# Sheet1.net
KiCad netlist of a schematic drawn in Altium Designer
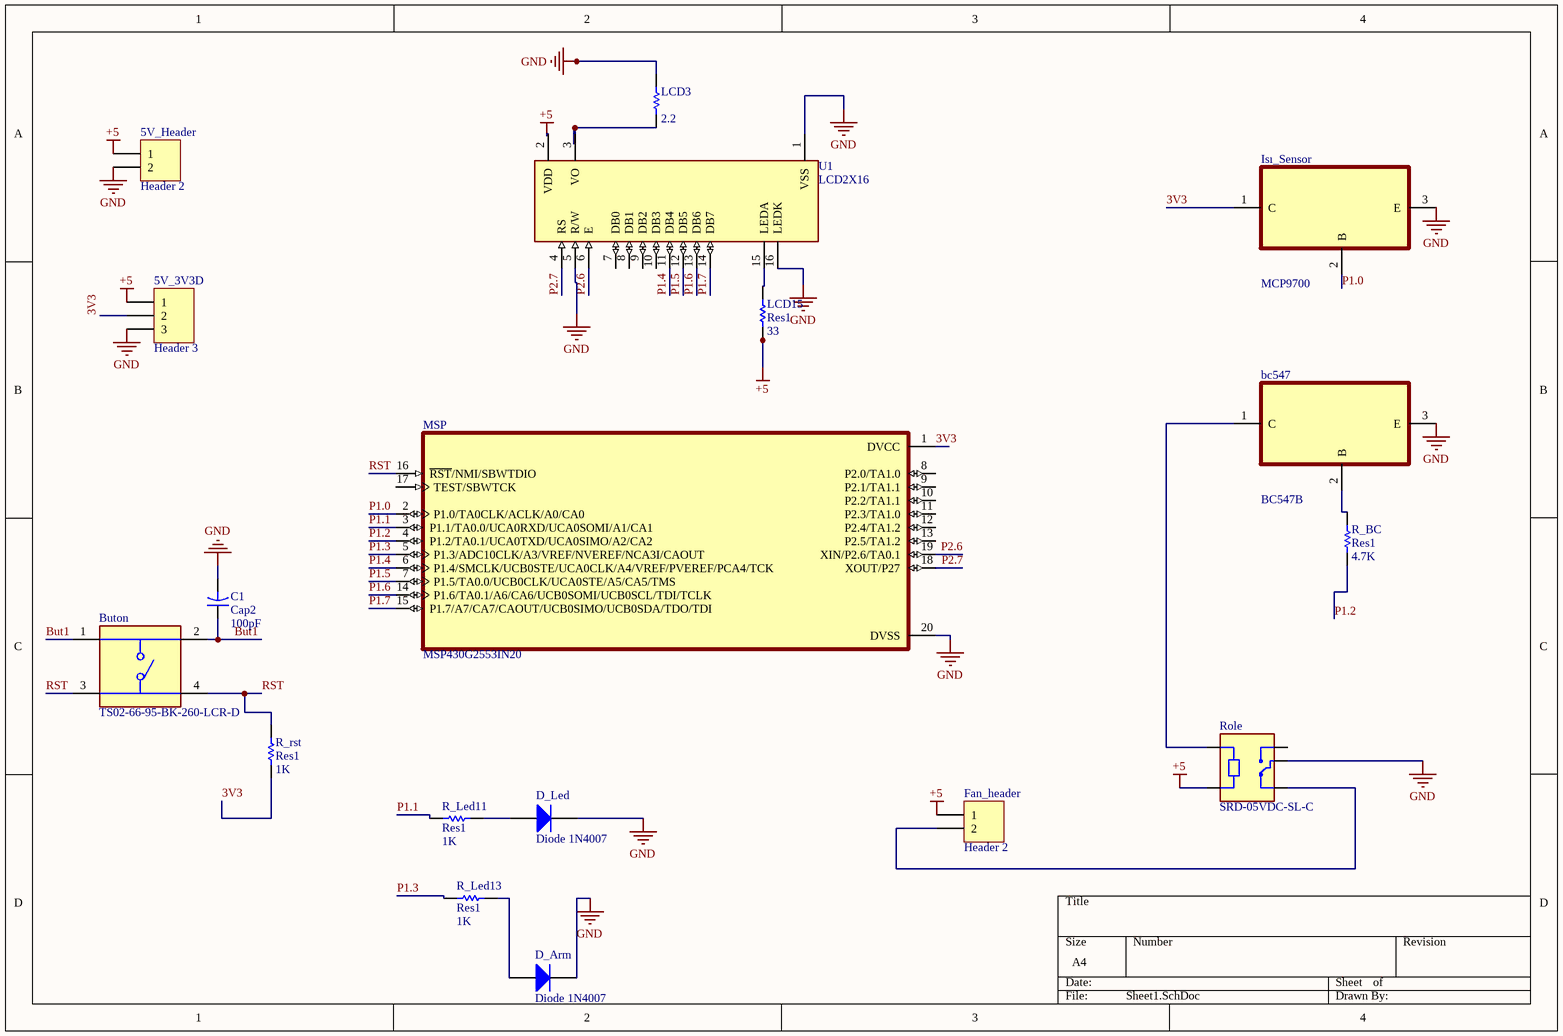
[diagram p0: Sheet1.SchDoc]

(export (version "E")
  (design (tool "Eeschema 10.0.6"))
  (components
    (comp (ref "5V_3V3D")
      (value "Header 3")
      (footprint "HDR1X3")
      (description "Header, 3-Pin")
      (fields (field (name "PUBLISHER") "Altium Limited"))
      (libsource (lib "Miscellaneous Connectors") (part "Header 3"))
    )
    (comp (ref "5V_Header")
      (value "Header 2")
      (footprint "HDR1X2")
      (description "Header, 2-Pin")
      (fields (field (name "PUBLISHER") "Altium Limited"))
      (libsource (lib "Miscellaneous Connectors") (part "Header 2"))
    )
    (comp (ref "bc547")
      (value "BC547B")
      (footprint "BC547B:TO127P254X732-3")
      (description "NPN Epitaxial Silicon Transistor")
      (fields (field (name "MF") "{'manufacturer': u'ON Semiconductor'}"))
      (libsource (lib "*") (part "BC547B"))
    )
    (comp (ref "Buton")
      (value "TS02-66-95-BK-260-LCR-D")
      (footprint "TS02-66-95-BK-260-LCR-D:SW_TS02-66-95-BK-260-LCR-D")
      (fields (field (name "MF") "{'manufacturer': u'CUI Devices'}"))
      (libsource (lib "*") (part "TS02-66-95-BK-260-LCR-D"))
    )
    (comp (ref "C1")
      (value "Cap2")
      (footprint "CAPR5-4X5")
      (description "Capacitor")
      (fields (field (name "ALTIUM_VALUE") "100pF") (field (name "PUBLISHER") "Altium Limited"))
      (libsource (lib "Miscellaneous Devices") (part "Cap2"))
    )
    (comp (ref "D_Arm")
      (value "Diode 1N4007")
      (footprint "DO-41")
      (description "1 Amp General Purpose Rectifier")
      (fields (field (name "PUBLISHER") "Altium Limited"))
      (libsource (lib "Miscellaneous Devices") (part "Diode 1N4007"))
    )
    (comp (ref "D_Led")
      (value "Diode 1N4007")
      (footprint "DO-41")
      (description "1 Amp General Purpose Rectifier")
      (fields (field (name "PUBLISHER") "Altium Limited"))
      (libsource (lib "Miscellaneous Devices") (part "Diode 1N4007"))
    )
    (comp (ref "Fan_header")
      (value "Header 2")
      (footprint "HDR1X2")
      (description "Header, 2-Pin")
      (fields (field (name "PUBLISHER") "Altium Limited"))
      (libsource (lib "Miscellaneous Connectors") (part "Header 2"))
    )
    (comp (ref "Isı_Sensor")
      (value "MCP9700")
      (footprint "BC547B:TO127P254X732-3")
      (description "NPN Epitaxial Silicon Transistor")
      (fields (field (name "MF") "{'manufacturer': u'ON Semiconductor'}") (field (name "MP") "BC547B"))
      (libsource (lib "*") (part "BC547B"))
    )
    (comp (ref "LCD3")
      (value "2.2")
      (footprint "AXIAL-0.3")
      (description "Resistor")
      (fields (field (name "PUBLISHER") "Altium Limited"))
      (libsource (lib "Miscellaneous Devices") (part "Res1"))
    )
    (comp (ref "LCD15")
      (value "Res1")
      (footprint "AXIAL-0.3")
      (description "Resistor")
      (fields (field (name "ALTIUM_VALUE") "33") (field (name "PUBLISHER") "Altium Limited"))
      (libsource (lib "Miscellaneous Devices") (part "Res1"))
    )
    (comp (ref "MSP")
      (value "MSP430G2553IN20")
      (footprint "MSP430G2553IN20:DIP794W45P254L2692H508Q20")
      (description "MSP430G2x53, MSP430G2x13 Mixed Signal Microcontroller 20-PDIP -40 to 85")
      (fields (field (name "MF") "{'manufacturer': u'Texas Instruments'}"))
      (libsource (lib "*") (part "MSP430G2553IN20"))
    )
    (comp (ref "Role")
      (value "SRD-05VDC-SL-C")
      (footprint "SRD-05VDC-SL-C:RELAY_SRD-05VDC-SL-C")
      (fields (field (name "MF") "{'manufacturer': u'Songle Relay'}"))
      (libsource (lib "*") (part "SRD-05VDC-SL-C"))
    )
    (comp (ref "R_BC")
      (value "Res1")
      (footprint "AXIAL-0.3")
      (description "Resistor")
      (fields (field (name "ALTIUM_VALUE") "4.7K") (field (name "PUBLISHER") "Altium Limited"))
      (libsource (lib "Miscellaneous Devices") (part "Res1"))
    )
    (comp (ref "R_Led11")
      (value "Res1")
      (footprint "AXIAL-0.3")
      (description "Resistor")
      (fields (field (name "ALTIUM_VALUE") "1K") (field (name "PUBLISHER") "Altium Limited"))
      (libsource (lib "Miscellaneous Devices") (part "Res1"))
    )
    (comp (ref "R_Led13")
      (value "Res1")
      (footprint "AXIAL-0.3")
      (description "Resistor")
      (fields (field (name "ALTIUM_VALUE") "1K") (field (name "PUBLISHER") "Altium Limited"))
      (libsource (lib "Miscellaneous Devices") (part "Res1"))
    )
    (comp (ref "R_rst")
      (value "Res1")
      (footprint "AXIAL-0.3")
      (description "Resistor")
      (fields (field (name "ALTIUM_VALUE") "1K") (field (name "PUBLISHER") "Altium Limited"))
      (libsource (lib "Miscellaneous Devices") (part "Res1"))
    )
    (comp (ref "U1")
      (value "LCD2X16")
      (footprint "LCD2X16:LCD_LCD2X16")
      (description "Display; Display: LCD 2x16 characters (blue backlight)")
      (fields (field (name "MF") "{'manufacturer': u'mikroElektronika'}"))
      (libsource (lib "*") (part "LCD2X16"))
    )
  )
  (nets
    (net (code "1") (name "+5") (class "Default")
      (node (ref "5V_3V3D") (pin "1") (pinfunction "1_1") (pintype "passive"))
      (node (ref "5V_Header") (pin "1") (pinfunction "1_1") (pintype "passive"))
      (node (ref "Fan_header") (pin "1") (pinfunction "1_1") (pintype "passive"))
      (node (ref "LCD15") (pin "2") (pinfunction "2_2") (pintype "passive"))
      (node (ref "Role") (pin "A2") (pinfunction "A2_A2") (pintype "passive"))
      (node (ref "U1") (pin "2") (pinfunction "VDD_2") (pintype "power_in"))
    )
    (net (code "2") (name "/3V3") (class "Default")
      (node (ref "5V_3V3D") (pin "2") (pinfunction "2_2") (pintype "passive"))
      (node (ref "Isı_Sensor") (pin "1") (pinfunction "C_1") (pintype "passive"))
      (node (ref "MSP") (pin "1") (pinfunction "DVCC_1") (pintype "power_in"))
      (node (ref "R_rst") (pin "2") (pinfunction "2_2") (pintype "passive"))
    )
    (net (code "3") (name "/But1") (class "Default")
      (node (ref "Buton") (pin "1") (pinfunction "1_1") (pintype "passive"))
      (node (ref "Buton") (pin "2") (pinfunction "2_2") (pintype "passive"))
      (node (ref "C1") (pin "1") (pinfunction "1_1") (pintype "passive"))
    )
    (net (code "4") (name "/P1.0") (class "Default")
      (node (ref "Isı_Sensor") (pin "2") (pinfunction "B_2") (pintype "passive"))
      (node (ref "MSP") (pin "2") (pinfunction "P1.0/TA0CLK/ACLK/A0/CA0_2") (pintype "bidirectional"))
    )
    (net (code "5") (name "/P1.1") (class "Default")
      (node (ref "MSP") (pin "3") (pinfunction "P1.1/TA0.0/UCA0RXD/UCA0SOMI/A1/CA1_3") (pintype "bidirectional"))
      (node (ref "R_Led11") (pin "1") (pinfunction "1_1") (pintype "passive"))
    )
    (net (code "6") (name "/P1.2") (class "Default")
      (node (ref "MSP") (pin "4") (pinfunction "P1.2/TA0.1/UCA0TXD/UCA0SIMO/A2/CA2_4") (pintype "bidirectional"))
      (node (ref "R_BC") (pin "2") (pinfunction "2_2") (pintype "passive"))
    )
    (net (code "7") (name "/P1.3") (class "Default")
      (node (ref "MSP") (pin "5") (pinfunction "P1.3/ADC10CLK/A3/VREF/NVEREF/NCA3I/CAOUT_5") (pintype "bidirectional"))
      (node (ref "R_Led13") (pin "1") (pinfunction "1_1") (pintype "passive"))
    )
    (net (code "8") (name "/P1.4") (class "Default")
      (node (ref "MSP") (pin "6") (pinfunction "P1.4/SMCLK/UCB0STE/UCA0CLK/A4/VREF/PVEREF/PCA4/TCK_6") (pintype "bidirectional"))
      (node (ref "U1") (pin "11") (pinfunction "DB4_11") (pintype "bidirectional"))
    )
    (net (code "9") (name "/P1.5") (class "Default")
      (node (ref "MSP") (pin "7") (pinfunction "P1.5/TA0.0/UCB0CLK/UCA0STE/A5/CA5/TMS_7") (pintype "bidirectional"))
      (node (ref "U1") (pin "12") (pinfunction "DB5_12") (pintype "bidirectional"))
    )
    (net (code "10") (name "/P1.6") (class "Default")
      (node (ref "MSP") (pin "14") (pinfunction "P1.6/TA0.1/A6/CA6/UCB0SOMI/UCB0SCL/TDI/TCLK_14") (pintype "bidirectional"))
      (node (ref "U1") (pin "13") (pinfunction "DB6_13") (pintype "bidirectional"))
    )
    (net (code "11") (name "/P1.7") (class "Default")
      (node (ref "MSP") (pin "15") (pinfunction "P1.7/A7/CA7/CAOUT/UCB0SIMO/UCB0SDA/TDO/TDI_15") (pintype "bidirectional"))
      (node (ref "U1") (pin "14") (pinfunction "DB7_14") (pintype "bidirectional"))
    )
    (net (code "12") (name "/P2.6") (class "Default")
      (node (ref "MSP") (pin "19") (pinfunction "XIN/P2.6/TA0.1_19") (pintype "bidirectional"))
      (node (ref "U1") (pin "6") (pinfunction "E_6") (pintype "input"))
    )
    (net (code "13") (name "/P2.7") (class "Default")
      (node (ref "MSP") (pin "18") (pinfunction "XOUT/P27_18") (pintype "bidirectional"))
      (node (ref "U1") (pin "4") (pinfunction "RS_4") (pintype "input"))
    )
    (net (code "14") (name "/RST") (class "Default")
      (node (ref "Buton") (pin "3") (pinfunction "3_3") (pintype "passive"))
      (node (ref "Buton") (pin "4") (pinfunction "4_4") (pintype "passive"))
      (node (ref "MSP") (pin "16") (pinfunction "~{RST}/NMI/SBWTDIO_16") (pintype "input"))
      (node (ref "R_rst") (pin "1") (pinfunction "1_1") (pintype "passive"))
    )
    (net (code "15") (name "GND") (class "Default")
      (node (ref "5V_3V3D") (pin "3") (pinfunction "3_3") (pintype "passive"))
      (node (ref "5V_Header") (pin "2") (pinfunction "2_2") (pintype "passive"))
      (node (ref "C1") (pin "2") (pinfunction "2_2") (pintype "passive"))
      (node (ref "D_Arm") (pin "2") (pinfunction "K_2") (pintype "passive"))
      (node (ref "D_Led") (pin "2") (pinfunction "K_2") (pintype "passive"))
      (node (ref "Isı_Sensor") (pin "3") (pinfunction "E_3") (pintype "passive"))
      (node (ref "LCD3") (pin "1") (pinfunction "1_1") (pintype "passive"))
      (node (ref "MSP") (pin "20") (pinfunction "DVSS_20") (pintype "power_in"))
      (node (ref "Role") (pin "COM") (pinfunction "COM_COM") (pintype "passive"))
      (node (ref "U1") (pin "1") (pinfunction "VSS_1") (pintype "power_in"))
      (node (ref "U1") (pin "16") (pinfunction "LEDK_16") (pintype "passive"))
      (node (ref "U1") (pin "5") (pinfunction "R/W_5") (pintype "input"))
      (node (ref "bc547") (pin "3") (pinfunction "E_3") (pintype "passive"))
    )
    (net (code "16") (name "Net-(D_Arm-A)") (class "Default")
      (node (ref "D_Arm") (pin "1") (pinfunction "A_1") (pintype "passive"))
      (node (ref "R_Led13") (pin "2") (pinfunction "2_2") (pintype "passive"))
    )
    (net (code "17") (name "Net-(D_Led-A)") (class "Default")
      (node (ref "D_Led") (pin "1") (pinfunction "A_1") (pintype "passive"))
      (node (ref "R_Led11") (pin "2") (pinfunction "2_2") (pintype "passive"))
    )
    (net (code "18") (name "Net-(Fan_header-Pad2)") (class "Default")
      (node (ref "Fan_header") (pin "2") (pinfunction "2_2") (pintype "passive"))
      (node (ref "Role") (pin "NC") (pinfunction "NC_NC") (pintype "passive"))
    )
    (net (code "19") (name "Net-(U1-LEDA)") (class "Default")
      (node (ref "LCD15") (pin "1") (pinfunction "1_1") (pintype "passive"))
      (node (ref "U1") (pin "15") (pinfunction "LEDA_15") (pintype "passive"))
    )
    (net (code "20") (name "Net-(U1-VO)") (class "Default")
      (node (ref "LCD3") (pin "2") (pinfunction "2_2") (pintype "passive"))
      (node (ref "U1") (pin "3") (pinfunction "VO_3") (pintype "passive"))
    )
    (net (code "21") (name "Net-(bc547-B)") (class "Default")
      (node (ref "R_BC") (pin "1") (pinfunction "1_1") (pintype "passive"))
      (node (ref "bc547") (pin "2") (pinfunction "B_2") (pintype "passive"))
    )
    (net (code "22") (name "Net-(bc547-C)") (class "Default")
      (node (ref "Role") (pin "A1") (pinfunction "A1_A1") (pintype "passive"))
      (node (ref "bc547") (pin "1") (pinfunction "C_1") (pintype "passive"))
    )
    (net (code "23") (name "unconnected-(MSP-P2.0{slash}TA1.0-Pad8)") (class "Default")
      (node (ref "MSP") (pin "8") (pinfunction "P2.0/TA1.0_8") (pintype "bidirectional"))
    )
    (net (code "24") (name "unconnected-(MSP-P2.1{slash}TA1.1-Pad9)") (class "Default")
      (node (ref "MSP") (pin "9") (pinfunction "P2.1/TA1.1_9") (pintype "bidirectional"))
    )
    (net (code "25") (name "unconnected-(MSP-P2.2{slash}TA1.1-Pad10)") (class "Default")
      (node (ref "MSP") (pin "10") (pinfunction "P2.2/TA1.1_10") (pintype "bidirectional"))
    )
    (net (code "26") (name "unconnected-(MSP-P2.3{slash}TA1.0-Pad11)") (class "Default")
      (node (ref "MSP") (pin "11") (pinfunction "P2.3/TA1.0_11") (pintype "bidirectional"))
    )
    (net (code "27") (name "unconnected-(MSP-P2.4{slash}TA1.2-Pad12)") (class "Default")
      (node (ref "MSP") (pin "12") (pinfunction "P2.4/TA1.2_12") (pintype "bidirectional"))
    )
    (net (code "28") (name "unconnected-(MSP-P2.5{slash}TA1.2-Pad13)") (class "Default")
      (node (ref "MSP") (pin "13") (pinfunction "P2.5/TA1.2_13") (pintype "bidirectional"))
    )
    (net (code "29") (name "unconnected-(MSP-TEST{slash}SBWTCK-Pad17)") (class "Default")
      (node (ref "MSP") (pin "17") (pinfunction "TEST/SBWTCK_17") (pintype "input"))
    )
    (net (code "30") (name "unconnected-(Role-PadNO)") (class "Default")
      (node (ref "Role") (pin "NO") (pinfunction "NO_NO") (pintype "passive"))
    )
    (net (code "31") (name "unconnected-(U1-DB0-Pad7)") (class "Default")
      (node (ref "U1") (pin "7") (pinfunction "DB0_7") (pintype "bidirectional"))
    )
    (net (code "32") (name "unconnected-(U1-DB1-Pad8)") (class "Default")
      (node (ref "U1") (pin "8") (pinfunction "DB1_8") (pintype "bidirectional"))
    )
    (net (code "33") (name "unconnected-(U1-DB2-Pad9)") (class "Default")
      (node (ref "U1") (pin "9") (pinfunction "DB2_9") (pintype "bidirectional"))
    )
    (net (code "34") (name "unconnected-(U1-DB3-Pad10)") (class "Default")
      (node (ref "U1") (pin "10") (pinfunction "DB3_10") (pintype "bidirectional"))
    )
  )
)
